# 1MHz_Osc.net
KiCad netlist of a schematic drawn in Altium Designer
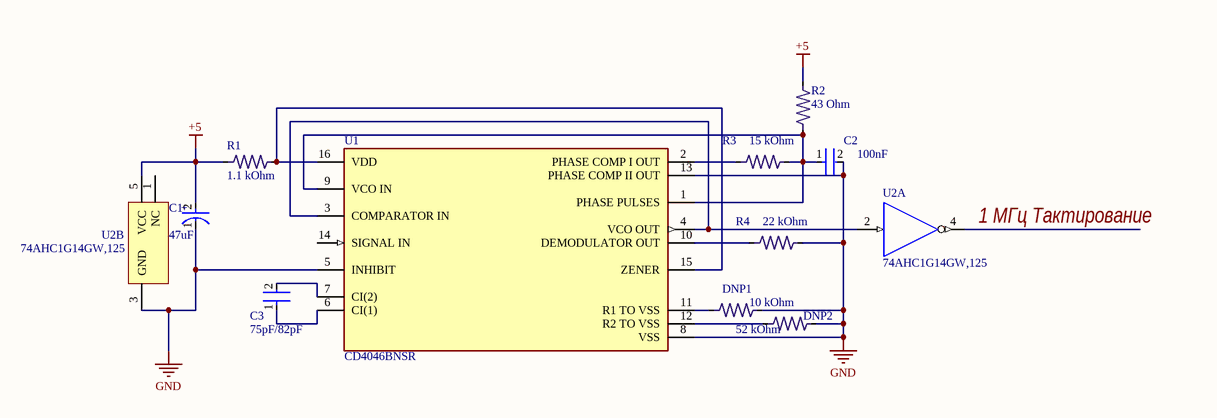
[diagram p0: 1MHz Osc.SchDoc]

(export (version "E")
  (design (tool "Eeschema 10.0.6"))
  (components
    (comp (ref "C1")
      (value "47uF")
      (footprint "FP-TAJB-MFG")
      (description "47uF 10V  ±10% 1Ω 1210  SMD Tantalum Capacitor")
      (fields (field (name "VOLTAGE") "10V") (field (name "TOLERANCE") "10%"))
      (libsource (lib "Altium Content Vault") (part "203bc49f2ac43e59fd269a8c329ed05"))
    )
    (comp (ref "C2")
      (value "100nF")
      (footprint "FP-0805-L_2_01_0_2-W_1_25-IPC_C")
      (description "CAP CER 0.1UF 50V X7R 0805")
      (fields (field (name "VOLTAGE") "50V") (field (name "TOLERANCE") "10%"))
      (libsource (lib "Altium Content Vault") (part "11868f565c42a9108669ba33697ecf6"))
    )
    (comp (ref "C3")
      (value "75pF/82pF")
      (footprint "FP-CL21-IPC_C")
      (description "CL21 Series 0805 75pF 50V ±5% Tolerance C0G Multilayer Ceramic Chip Capacitor")
      (fields (field (name "TOLERANCE") "5%") (field (name "Comment") "CL21C750JBANNNC"))
      (libsource (lib "Altium Content Vault") (part "b4654b650e69147ec39a6b967a45e02"))
    )
    (comp (ref "DNP1")
      (value "10 kOhm")
      (footprint "RES0805")
      (fields (field (name "TOLERANCE") "1%") (field (name "Comment") "DNP"))
      (libsource (lib "res0805") (part "DNP"))
    )
    (comp (ref "DNP2")
      (value "52 kOhm")
      (footprint "RES0805")
      (fields (field (name "TOLERANCE") "1%") (field (name "Comment") "DNP"))
      (libsource (lib "res0805") (part "DNP"))
    )
    (comp (ref "R1")
      (value "1.1 kOhm")
      (footprint "RES0805")
      (fields (field (name "TOLERANCE") "1%") (field (name "Comment") "kOhm 1%"))
      (libsource (lib "res0805") (part "kOhm 1%"))
    )
    (comp (ref "R2")
      (value "43 Ohm")
      (footprint "RES0805")
      (fields (field (name "TOLERANCE") "1%") (field (name "Comment") "Ohm 1%"))
      (libsource (lib "res0805") (part "Ohm 1%"))
    )
    (comp (ref "R3")
      (value "15 kOhm")
      (footprint "RES0805")
      (fields (field (name "TOLERANCE") "1%") (field (name "Comment") "kOhm 1%"))
      (libsource (lib "res0805") (part "kOhm 1%"))
    )
    (comp (ref "R4")
      (value "22 kOhm")
      (footprint "RES0805")
      (fields (field (name "TOLERANCE") "1%") (field (name "Comment") "kOhm 1%"))
      (libsource (lib "res0805") (part "kOhm 1%"))
    )
    (comp (ref "U1")
      (value "CD4046BNSR")
      (footprint "FP-NS0016A-IPC_C")
      (description "IC PHASE-LOCK LOOP MCPWR 16SO")
      (libsource (lib "Altium Content Vault") (part "d620af922e5c33b18a72015a0af63fb"))
    )
    (comp (ref "U2")
      (value "74AHC1G14GW,125")
      (footprint "NXP-SOT353-1_L")
      (description "Inverting Schmitt Trigger, 1 uA, 2 to 5.5 V, -40 to 125 degC, 5-Pin TSSOP (SOT353-1), RoHS, Reel")
      (fields (field (name "MANUFACTURER") "NXP Semiconductors"))
      (libsource (lib "") (part "NXP-74AHCX1G14-5_1"))
    )
  )
  (nets
    (net (code "1") (name "+5") (class "Default")
      (node (ref "C1") (pin "2") (pinfunction "A_2") (pintype "passive"))
      (node (ref "R1") (pin "1") (pinfunction "1_1") (pintype "passive"))
      (node (ref "R2") (pin "2") (pinfunction "2_2") (pintype "passive"))
      (node (ref "U2") (pin "5") (pinfunction "VCC_5") (pintype "power_in"))
    )
    (net (code "2") (name "/1 МГц Тактирование") (class "Default")
      (node (ref "U2") (pin "4") (pinfunction "~{Y}_4") (pintype "output"))
    )
    (net (code "3") (name "GND") (class "Default")
      (node (ref "C1") (pin "1") (pinfunction "C_1") (pintype "passive"))
      (node (ref "C2") (pin "2") (pinfunction "2_2") (pintype "passive"))
      (node (ref "DNP1") (pin "2") (pinfunction "2_2") (pintype "passive"))
      (node (ref "DNP2") (pin "2") (pinfunction "2_2") (pintype "passive"))
      (node (ref "R4") (pin "2") (pinfunction "2_2") (pintype "passive"))
      (node (ref "U1") (pin "13") (pinfunction "PHASE_COMP_II_OUT_13") (pintype "passive"))
      (node (ref "U1") (pin "5") (pinfunction "INHIBIT_5") (pintype "passive"))
      (node (ref "U1") (pin "8") (pinfunction "VSS_8") (pintype "power_in"))
      (node (ref "U2") (pin "3") (pinfunction "GND_3") (pintype "power_in"))
    )
    (net (code "4") (name "Net-(U1-CI(1))") (class "Default")
      (node (ref "C3") (pin "1") (pinfunction "1_1") (pintype "passive"))
      (node (ref "U1") (pin "6") (pinfunction "CI(1)_6") (pintype "passive"))
    )
    (net (code "5") (name "Net-(U1-CI(2))") (class "Default")
      (node (ref "C3") (pin "2") (pinfunction "2_2") (pintype "passive"))
      (node (ref "U1") (pin "7") (pinfunction "CI(2)_7") (pintype "passive"))
    )
    (net (code "6") (name "Net-(U1-COMPARATOR_IN)") (class "Default")
      (node (ref "U1") (pin "3") (pinfunction "COMPARATOR_IN_3") (pintype "passive"))
      (node (ref "U1") (pin "4") (pinfunction "VCO_OUT_4") (pintype "output"))
      (node (ref "U2") (pin "2") (pinfunction "A_2") (pintype "input"))
    )
    (net (code "7") (name "Net-(U1-DEMODULATOR_OUT)") (class "Default")
      (node (ref "R4") (pin "1") (pinfunction "1_1") (pintype "passive"))
      (node (ref "U1") (pin "10") (pinfunction "DEMODULATOR_OUT_10") (pintype "passive"))
    )
    (net (code "8") (name "Net-(U1-PHASE_COMP_I_OUT)") (class "Default")
      (node (ref "R3") (pin "1") (pinfunction "1_1") (pintype "passive"))
      (node (ref "U1") (pin "2") (pinfunction "PHASE_COMP_I_OUT_2") (pintype "passive"))
    )
    (net (code "9") (name "Net-(U1-PHASE_PULSES)") (class "Default")
      (node (ref "C2") (pin "1") (pinfunction "1_1") (pintype "passive"))
      (node (ref "R2") (pin "1") (pinfunction "1_1") (pintype "passive"))
      (node (ref "R3") (pin "2") (pinfunction "2_2") (pintype "passive"))
      (node (ref "U1") (pin "1") (pinfunction "PHASE_PULSES_1") (pintype "passive"))
      (node (ref "U1") (pin "9") (pinfunction "VCO_IN_9") (pintype "power_in"))
    )
    (net (code "10") (name "Net-(U1-R1_TO_VSS)") (class "Default")
      (node (ref "DNP1") (pin "1") (pinfunction "1_1") (pintype "passive"))
      (node (ref "U1") (pin "11") (pinfunction "R1_TO_VSS_11") (pintype "passive"))
    )
    (net (code "11") (name "Net-(U1-R2_TO_VSS)") (class "Default")
      (node (ref "DNP2") (pin "1") (pinfunction "1_1") (pintype "passive"))
      (node (ref "U1") (pin "12") (pinfunction "R2_TO_VSS_12") (pintype "passive"))
    )
    (net (code "12") (name "Net-(U1-VDD)") (class "Default")
      (node (ref "R1") (pin "2") (pinfunction "2_2") (pintype "passive"))
      (node (ref "U1") (pin "15") (pinfunction "ZENER_15") (pintype "passive"))
      (node (ref "U1") (pin "16") (pinfunction "VDD_16") (pintype "power_in"))
    )
    (net (code "13") (name "unconnected-(U1-SIGNAL_IN-Pad14)") (class "Default")
      (node (ref "U1") (pin "14") (pinfunction "SIGNAL_IN_14") (pintype "input"))
    )
    (net (code "14") (name "unconnected-(U2B-NC-Pad1)") (class "Default")
      (node (ref "U2") (pin "1") (pinfunction "NC_1") (pintype "passive"))
    )
  )
)
